# LCD.net
KiCad netlist of a schematic drawn in Altium Designer
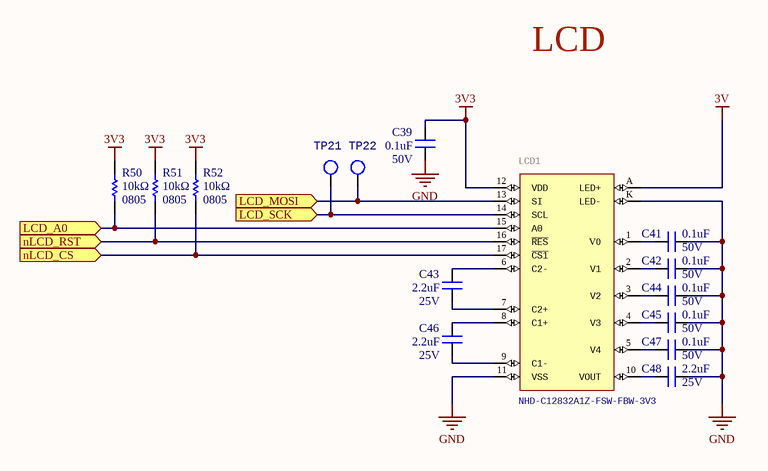
[diagram p0: LCD.SchDoc]

(export (version "E")
  (design (tool "Eeschema 10.0.6"))
  (components
    (comp (ref "C39")
      (value "0.1uF")
      (footprint "CAPC2012X140N")
      (description "CAP CER 0.1UF 50V X7R 0805")
      (fields
        (field (name "TOLERANCE") "10%")
        (field (name "VOLTAGE RATING") "50V")
        (field (name "Comment") "CAP_0.1uF_50V_0805")
      )
      (libsource (lib "UWRT_Schematic_Library_2020") (part "CAP_0.1uF_50V_0805"))
    )
    (comp (ref "C41")
      (value "0.1uF")
      (footprint "CAPC2012X140N")
      (description "CAP CER 0.1UF 50V X7R 0805")
      (fields
        (field (name "TOLERANCE") "10%")
        (field (name "VOLTAGE RATING") "50V")
        (field (name "Comment") "CAP_0.1uF_50V_0805")
      )
      (libsource (lib "UWRT_Schematic_Library_2020") (part "CAP_0.1uF_50V_0805"))
    )
    (comp (ref "C42")
      (value "0.1uF")
      (footprint "CAPC2012X140N")
      (description "CAP CER 0.1UF 50V X7R 0805")
      (fields
        (field (name "TOLERANCE") "10%")
        (field (name "VOLTAGE RATING") "50V")
        (field (name "Comment") "CAP_0.1uF_50V_0805")
      )
      (libsource (lib "UWRT_Schematic_Library_2020") (part "CAP_0.1uF_50V_0805"))
    )
    (comp (ref "C43")
      (value "2.2uF")
      (footprint "CAPC2012X140N")
      (description "CAP CER 2.2UF 25V X7R 0805")
      (fields
        (field (name "TOLERANCE") "10%")
        (field (name "VOLTAGE RATING") "25V")
        (field (name "Comment") "CAP_2.2uF_25V_0805")
      )
      (libsource (lib "UWRT_Schematic_Library_2020") (part "CAP_2.2uF_25V_0805"))
    )
    (comp (ref "C44")
      (value "0.1uF")
      (footprint "CAPC2012X140N")
      (description "CAP CER 0.1UF 50V X7R 0805")
      (fields
        (field (name "TOLERANCE") "10%")
        (field (name "VOLTAGE RATING") "50V")
        (field (name "Comment") "CAP_0.1uF_50V_0805")
      )
      (libsource (lib "UWRT_Schematic_Library_2020") (part "CAP_0.1uF_50V_0805"))
    )
    (comp (ref "C45")
      (value "0.1uF")
      (footprint "CAPC2012X140N")
      (description "CAP CER 0.1UF 50V X7R 0805")
      (fields
        (field (name "TOLERANCE") "10%")
        (field (name "VOLTAGE RATING") "50V")
        (field (name "Comment") "CAP_0.1uF_50V_0805")
      )
      (libsource (lib "UWRT_Schematic_Library_2020") (part "CAP_0.1uF_50V_0805"))
    )
    (comp (ref "C46")
      (value "2.2uF")
      (footprint "CAPC2012X140N")
      (description "CAP CER 2.2UF 25V X7R 0805")
      (fields
        (field (name "TOLERANCE") "10%")
        (field (name "VOLTAGE RATING") "25V")
        (field (name "Comment") "CAP_2.2uF_25V_0805")
      )
      (libsource (lib "UWRT_Schematic_Library_2020") (part "CAP_2.2uF_25V_0805"))
    )
    (comp (ref "C47")
      (value "0.1uF")
      (footprint "CAPC2012X140N")
      (description "CAP CER 0.1UF 50V X7R 0805")
      (fields
        (field (name "TOLERANCE") "10%")
        (field (name "VOLTAGE RATING") "50V")
        (field (name "Comment") "CAP_0.1uF_50V_0805")
      )
      (libsource (lib "UWRT_Schematic_Library_2020") (part "CAP_0.1uF_50V_0805"))
    )
    (comp (ref "C48")
      (value "2.2uF")
      (footprint "CAPC2012X140N")
      (description "CAP CER 2.2UF 25V X7R 0805")
      (fields
        (field (name "TOLERANCE") "10%")
        (field (name "VOLTAGE RATING") "25V")
        (field (name "Comment") "CAP_2.2uF_25V_0805")
      )
      (libsource (lib "UWRT_Schematic_Library_2020") (part "CAP_2.2uF_25V_0805"))
    )
    (comp (ref "LCD1")
      (value "NHD-C12832A1Z-FSW-FBW-3V3")
      (footprint "NHDC12832A1ZFSWFBW3V3")
      (description "LCD COG GRAPHIC 128X32")
      (libsource (lib "UWRT_Schematic_Library_2020") (part "NHD-C12832A1Z-FSW-FBW-3V3"))
    )
    (comp (ref "R50")
      (value "10kΩ")
      (footprint "RESC2012X60N")
      (description "RES SMD 10K OHM 1% 1/8W 0805")
      (fields
        (field (name "CASE CODE (IMPERIAL)") "0805")
        (field (name "TOLERANCE") "1%")
        (field (name "Comment") "RES_10kΩ_0805")
      )
      (libsource (lib "UWRT_Schematic_Library_2020") (part "RES_10kΩ_0805"))
    )
    (comp (ref "R51")
      (value "10kΩ")
      (footprint "RESC2012X60N")
      (description "RES SMD 10K OHM 1% 1/8W 0805")
      (fields
        (field (name "CASE CODE (IMPERIAL)") "0805")
        (field (name "TOLERANCE") "1%")
        (field (name "Comment") "RES_10kΩ_0805")
      )
      (libsource (lib "UWRT_Schematic_Library_2020") (part "RES_10kΩ_0805"))
    )
    (comp (ref "R52")
      (value "10kΩ")
      (footprint "RESC2012X60N")
      (description "RES SMD 10K OHM 1% 1/8W 0805")
      (fields
        (field (name "CASE CODE (IMPERIAL)") "0805")
        (field (name "TOLERANCE") "1%")
        (field (name "Comment") "RES_10kΩ_0805")
      )
      (libsource (lib "UWRT_Schematic_Library_2020") (part "RES_10kΩ_0805"))
    )
    (comp (ref "TP21")
      (value "TESTPOINT_LOOP")
      (footprint "TESTPOINT_LOOP")
      (description "Loop testpoint through-hole pad")
      (libsource (lib "UWRT_Schematic_Library_2020") (part "TESTPOINT_LOOP"))
    )
    (comp (ref "TP22")
      (value "TESTPOINT_LOOP")
      (footprint "TESTPOINT_LOOP")
      (description "Loop testpoint through-hole pad")
      (libsource (lib "UWRT_Schematic_Library_2020") (part "TESTPOINT_LOOP"))
    )
  )
  (nets
    (net (code "1") (name "/LCD_A0") (class "Default")
      (node (ref "LCD1") (pin "15") (pinfunction "A0_15") (pintype "bidirectional"))
      (node (ref "R50") (pin "1") (pinfunction "1_1") (pintype "passive"))
    )
    (net (code "2") (name "/LCD_MOSI") (class "Default")
      (node (ref "LCD1") (pin "13") (pinfunction "SI_13") (pintype "bidirectional"))
      (node (ref "TP22") (pin "1") (pintype "passive"))
    )
    (net (code "3") (name "/LCD_SCK") (class "Default")
      (node (ref "LCD1") (pin "14") (pinfunction "SCL_14") (pintype "bidirectional"))
      (node (ref "TP21") (pin "1") (pintype "passive"))
    )
    (net (code "4") (name "/nLCD_CS") (class "Default")
      (node (ref "LCD1") (pin "17") (pinfunction "~{CS1}_17") (pintype "bidirectional"))
      (node (ref "R52") (pin "1") (pinfunction "1_1") (pintype "passive"))
    )
    (net (code "5") (name "/nLCD_RST") (class "Default")
      (node (ref "LCD1") (pin "16") (pinfunction "~{RES}_16") (pintype "bidirectional"))
      (node (ref "R51") (pin "1") (pinfunction "1_1") (pintype "passive"))
    )
    (net (code "6") (name "3V") (class "Default")
      (node (ref "LCD1") (pin "A") (pinfunction "LED+_A") (pintype "bidirectional"))
    )
    (net (code "7") (name "3V3") (class "Default")
      (node (ref "C39") (pin "1") (pinfunction "1_1") (pintype "passive"))
      (node (ref "LCD1") (pin "12") (pinfunction "VDD_12") (pintype "bidirectional"))
      (node (ref "R50") (pin "2") (pinfunction "2_2") (pintype "passive"))
      (node (ref "R51") (pin "2") (pinfunction "2_2") (pintype "passive"))
      (node (ref "R52") (pin "2") (pinfunction "2_2") (pintype "passive"))
    )
    (net (code "8") (name "GND") (class "Default")
      (node (ref "C39") (pin "2") (pinfunction "2_2") (pintype "passive"))
      (node (ref "C41") (pin "1") (pinfunction "1_1") (pintype "passive"))
      (node (ref "C42") (pin "1") (pinfunction "1_1") (pintype "passive"))
      (node (ref "C44") (pin "1") (pinfunction "1_1") (pintype "passive"))
      (node (ref "C45") (pin "1") (pinfunction "1_1") (pintype "passive"))
      (node (ref "C47") (pin "1") (pinfunction "1_1") (pintype "passive"))
      (node (ref "C48") (pin "1") (pinfunction "1_1") (pintype "passive"))
      (node (ref "LCD1") (pin "11") (pinfunction "VSS_11") (pintype "bidirectional"))
      (node (ref "LCD1") (pin "K") (pinfunction "LED-_K") (pintype "bidirectional"))
    )
    (net (code "9") (name "Net-(LCD1-C1+)") (class "Default")
      (node (ref "C46") (pin "2") (pinfunction "2_2") (pintype "passive"))
      (node (ref "LCD1") (pin "8") (pinfunction "C1+_8") (pintype "bidirectional"))
    )
    (net (code "10") (name "Net-(LCD1-C1-)") (class "Default")
      (node (ref "C46") (pin "1") (pinfunction "1_1") (pintype "passive"))
      (node (ref "LCD1") (pin "9") (pinfunction "C1-_9") (pintype "bidirectional"))
    )
    (net (code "11") (name "Net-(LCD1-C2+)") (class "Default")
      (node (ref "C43") (pin "1") (pinfunction "1_1") (pintype "passive"))
      (node (ref "LCD1") (pin "7") (pinfunction "C2+_7") (pintype "bidirectional"))
    )
    (net (code "12") (name "Net-(LCD1-C2-)") (class "Default")
      (node (ref "C43") (pin "2") (pinfunction "2_2") (pintype "passive"))
      (node (ref "LCD1") (pin "6") (pinfunction "C2-_6") (pintype "bidirectional"))
    )
    (net (code "13") (name "Net-(LCD1-V0)") (class "Default")
      (node (ref "C41") (pin "2") (pinfunction "2_2") (pintype "passive"))
      (node (ref "LCD1") (pin "1") (pinfunction "V0_1") (pintype "bidirectional"))
    )
    (net (code "14") (name "Net-(LCD1-V1)") (class "Default")
      (node (ref "C42") (pin "2") (pinfunction "2_2") (pintype "passive"))
      (node (ref "LCD1") (pin "2") (pinfunction "V1_2") (pintype "bidirectional"))
    )
    (net (code "15") (name "Net-(LCD1-V2)") (class "Default")
      (node (ref "C44") (pin "2") (pinfunction "2_2") (pintype "passive"))
      (node (ref "LCD1") (pin "3") (pinfunction "V2_3") (pintype "bidirectional"))
    )
    (net (code "16") (name "Net-(LCD1-V3)") (class "Default")
      (node (ref "C45") (pin "2") (pinfunction "2_2") (pintype "passive"))
      (node (ref "LCD1") (pin "4") (pinfunction "V3_4") (pintype "bidirectional"))
    )
    (net (code "17") (name "Net-(LCD1-V4)") (class "Default")
      (node (ref "C47") (pin "2") (pinfunction "2_2") (pintype "passive"))
      (node (ref "LCD1") (pin "5") (pinfunction "V4_5") (pintype "bidirectional"))
    )
    (net (code "18") (name "Net-(LCD1-VOUT)") (class "Default")
      (node (ref "C48") (pin "2") (pinfunction "2_2") (pintype "passive"))
      (node (ref "LCD1") (pin "10") (pinfunction "VOUT_10") (pintype "bidirectional"))
    )
  )
)
